# guac_v1.net
KiCad netlist of a schematic drawn in EAGLE
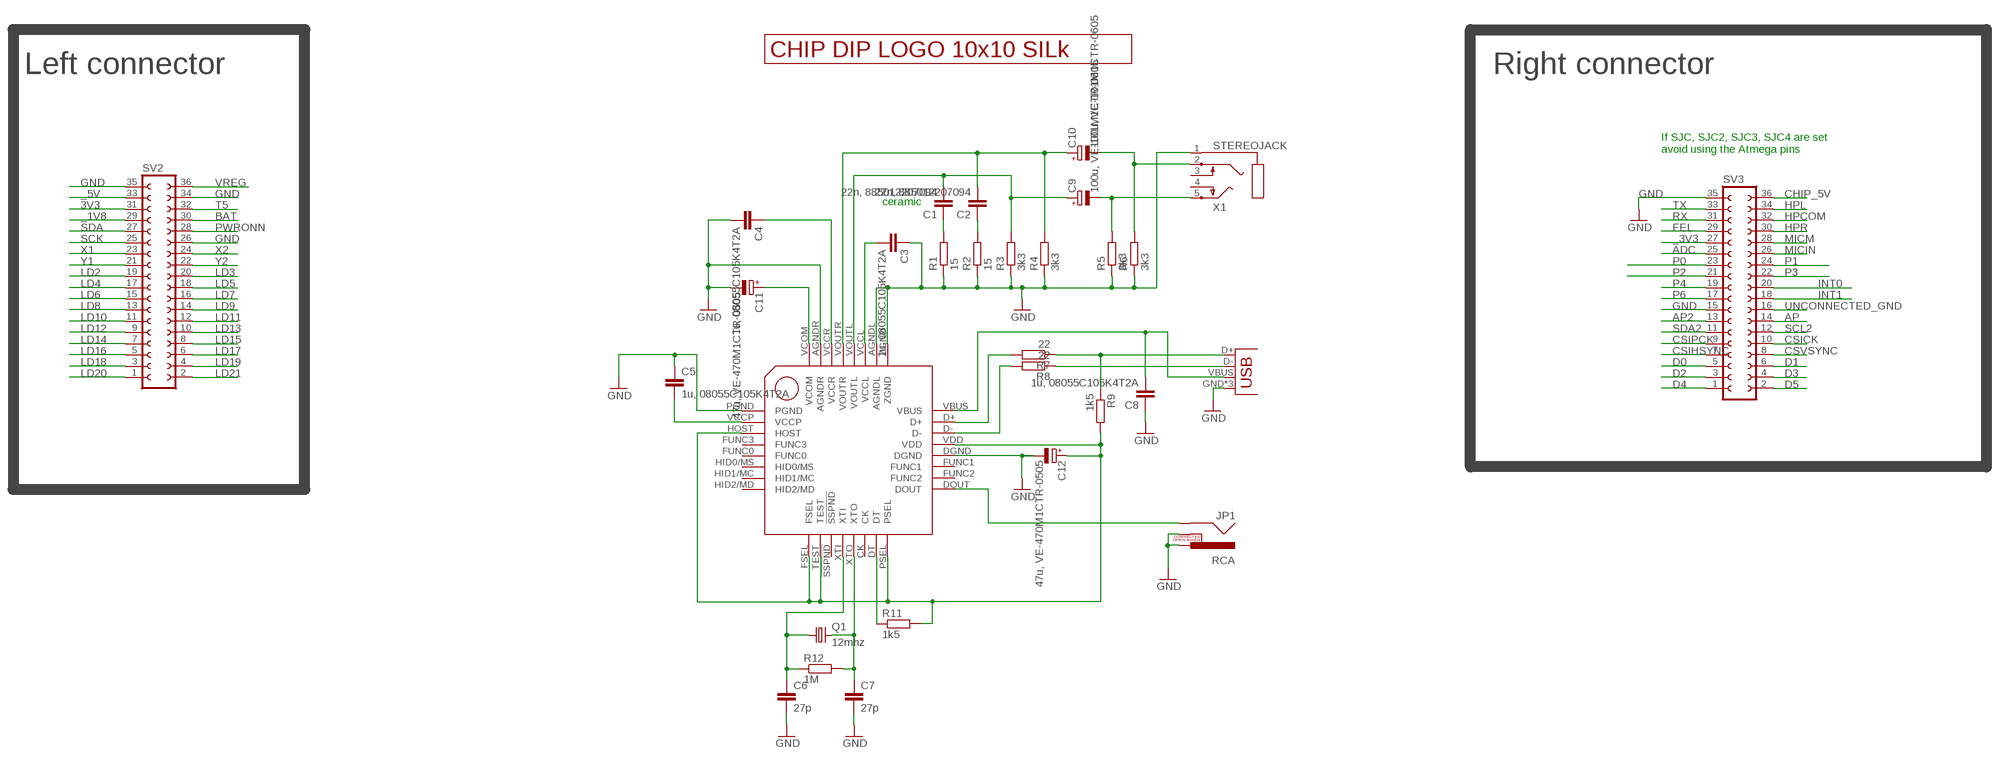
[diagram p0: schematic, sheet 1]

(export (version "E")
  (design (tool "Eeschema 10.0.6"))
  (components
    (comp (ref "C1")
      (value "22n, 885012207094")
      (footprint "eagle-import:C0805")
      (libsource (lib "eagle-import") (part "C-EUC0805"))
    )
    (comp (ref "C2")
      (value "22n, 885012207094")
      (footprint "eagle-import:C0805")
      (libsource (lib "eagle-import") (part "C-EUC0805"))
    )
    (comp (ref "C3")
      (value "1u, 08055C105K4T2A")
      (footprint "eagle-import:C0805")
      (libsource (lib "eagle-import") (part "C-EUC0805"))
    )
    (comp (ref "C4")
      (value "1u, 08055C105K4T2A")
      (footprint "eagle-import:C0805")
      (libsource (lib "eagle-import") (part "C-EUC0805"))
    )
    (comp (ref "C5")
      (value "1u, 08055C105K4T2A")
      (footprint "eagle-import:C0805")
      (libsource (lib "eagle-import") (part "C-EUC0805"))
    )
    (comp (ref "C6")
      (value "27p")
      (footprint "eagle-import:C0805")
      (libsource (lib "eagle-import") (part "C-EUC0805"))
    )
    (comp (ref "C7")
      (value "27p")
      (footprint "eagle-import:C0805")
      (libsource (lib "eagle-import") (part "C-EUC0805"))
    )
    (comp (ref "C8")
      (value "1u, 08055C105K4T2A")
      (footprint "eagle-import:C0805")
      (libsource (lib "eagle-import") (part "C-EUC0805"))
    )
    (comp (ref "C9")
      (value "100u, VE-101M1CTR-0605")
      (footprint "eagle-import:140CLH-0810")
      (libsource (lib "eagle-import") (part "CPOL-EU140CLH-0810"))
    )
    (comp (ref "C10")
      (value "100u, VE-101M1CTR-0605")
      (footprint "eagle-import:140CLH-0810")
      (libsource (lib "eagle-import") (part "CPOL-EU140CLH-0810"))
    )
    (comp (ref "C11")
      (value "47u, VE-470M1CTR-0505")
      (footprint "eagle-import:140CLH-0810")
      (libsource (lib "eagle-import") (part "CPOL-EU140CLH-0810"))
    )
    (comp (ref "C12")
      (value "47u, VE-470M1CTR-0505")
      (footprint "eagle-import:140CLH-0810")
      (libsource (lib "eagle-import") (part "CPOL-EU140CLH-0810"))
    )
    (comp (ref "JP1")
      (value "RCA")
      (footprint "eagle-import:RCA")
      (libsource (lib "eagle-import") (part "RCA"))
    )
    (comp (ref "Q1")
      (value "12mhz")
      (footprint "eagle-import:HC49UP")
      (libsource (lib "eagle-import") (part "CRYSTALHC49UP"))
    )
    (comp (ref "R1")
      (value "15")
      (footprint "eagle-import:M0805")
      (libsource (lib "eagle-import") (part "R-EU_M0805"))
    )
    (comp (ref "R2")
      (value "15")
      (footprint "eagle-import:M0805")
      (libsource (lib "eagle-import") (part "R-EU_M0805"))
    )
    (comp (ref "R3")
      (value "3k3")
      (footprint "eagle-import:M0805")
      (libsource (lib "eagle-import") (part "R-EU_M0805"))
    )
    (comp (ref "R4")
      (value "3k3")
      (footprint "eagle-import:M0805")
      (libsource (lib "eagle-import") (part "R-EU_M0805"))
    )
    (comp (ref "R5")
      (value "3k3")
      (footprint "eagle-import:M0805")
      (libsource (lib "eagle-import") (part "R-EU_M0805"))
    )
    (comp (ref "R6")
      (value "3k3")
      (footprint "eagle-import:M0805")
      (libsource (lib "eagle-import") (part "R-EU_M0805"))
    )
    (comp (ref "R7")
      (value "22")
      (footprint "eagle-import:M0805")
      (libsource (lib "eagle-import") (part "R-EU_M0805"))
    )
    (comp (ref "R8")
      (value "22")
      (footprint "eagle-import:M0805")
      (libsource (lib "eagle-import") (part "R-EU_M0805"))
    )
    (comp (ref "R9")
      (value "1k5")
      (footprint "eagle-import:M0805")
      (libsource (lib "eagle-import") (part "R-EU_M0805"))
    )
    (comp (ref "R11")
      (value "1k5")
      (footprint "eagle-import:M0805")
      (libsource (lib "eagle-import") (part "R-EU_M0805"))
    )
    (comp (ref "R12")
      (value "1M")
      (footprint "eagle-import:M0805")
      (libsource (lib "eagle-import") (part "R-EU_M0805"))
    )
    (comp (ref "SV2")
      (value "FE18-2")
      (footprint "eagle-import:FE18-2")
      (libsource (lib "eagle-import") (part "FE18-2"))
    )
    (comp (ref "SV3")
      (value "FE18-2")
      (footprint "eagle-import:FE18-2")
      (libsource (lib "eagle-import") (part "FE18-2"))
    )
    (comp (ref "U$1")
      (value "PCM2706")
      (footprint "eagle-import:TQFP32-08")
      (libsource (lib "eagle-import") (part "PCM2706"))
    )
    (comp (ref "U$3")
      (value "LOGO_10X10_SILK")
      (footprint "eagle-import:LOGO_10X10_SILK")
      (libsource (lib "eagle-import") (part "LOGO_10X10_SILK"))
    )
    (comp (ref "USB")
      (value "USBUSB-MICROB-SMT-DIP")
      (footprint "eagle-import:USB-MICROB-SMT-DIP")
      (libsource (lib "eagle-import") (part "USBUSB-MICROB-SMT-DIP"))
    )
    (comp (ref "X1")
      (value "STEREOJACK")
      (footprint "eagle-import:STX3100")
      (libsource (lib "eagle-import") (part "STEREOJACK"))
    )
  )
  (nets
    (net (code "1") (name "/3V3") (class "Default")
      (node (ref "SV2") (pin "31") (pinfunction "31_31") (pintype "passive"))
    )
    (net (code "2") (name "/ADC") (class "Default")
      (node (ref "SV3") (pin "25") (pinfunction "25_25") (pintype "passive"))
    )
    (net (code "3") (name "/AP") (class "Default")
      (node (ref "SV3") (pin "14") (pinfunction "14_14") (pintype "passive"))
    )
    (net (code "4") (name "/AP2") (class "Default")
      (node (ref "SV3") (pin "13") (pinfunction "13_13") (pintype "passive"))
    )
    (net (code "5") (name "/BAT") (class "Default")
      (node (ref "SV2") (pin "30") (pinfunction "30_30") (pintype "passive"))
    )
    (net (code "6") (name "/CHIP_5V") (class "Default")
      (node (ref "SV3") (pin "36") (pinfunction "36_36") (pintype "passive"))
    )
    (net (code "7") (name "/CSICK") (class "Default")
      (node (ref "SV3") (pin "10") (pinfunction "10_10") (pintype "passive"))
    )
    (net (code "8") (name "/CSIHSYNC") (class "Default")
      (node (ref "SV3") (pin "7") (pinfunction "7_7") (pintype "passive"))
    )
    (net (code "9") (name "/CSIPCK") (class "Default")
      (node (ref "SV3") (pin "9") (pinfunction "9_9") (pintype "passive"))
    )
    (net (code "10") (name "/CSVSYNC") (class "Default")
      (node (ref "SV3") (pin "8") (pinfunction "8_8") (pintype "passive"))
    )
    (net (code "11") (name "/D0") (class "Default")
      (node (ref "SV3") (pin "5") (pinfunction "5_5") (pintype "passive"))
    )
    (net (code "12") (name "/D1") (class "Default")
      (node (ref "SV3") (pin "6") (pinfunction "6_6") (pintype "passive"))
    )
    (net (code "13") (name "/D2") (class "Default")
      (node (ref "SV3") (pin "3") (pinfunction "3_3") (pintype "passive"))
    )
    (net (code "14") (name "/D3") (class "Default")
      (node (ref "SV3") (pin "4") (pinfunction "4_4") (pintype "passive"))
    )
    (net (code "15") (name "/D4") (class "Default")
      (node (ref "SV3") (pin "1") (pinfunction "1_1") (pintype "passive"))
    )
    (net (code "16") (name "/D5") (class "Default")
      (node (ref "SV3") (pin "2") (pinfunction "2_2") (pintype "passive"))
    )
    (net (code "17") (name "/FEL") (class "Default")
      (node (ref "SV3") (pin "29") (pinfunction "29_29") (pintype "passive"))
    )
    (net (code "18") (name "/HPCOM") (class "Default")
      (node (ref "SV3") (pin "32") (pinfunction "32_32") (pintype "passive"))
    )
    (net (code "19") (name "/HPL") (class "Default")
      (node (ref "SV3") (pin "34") (pinfunction "34_34") (pintype "passive"))
    )
    (net (code "20") (name "/HPR") (class "Default")
      (node (ref "SV3") (pin "30") (pinfunction "30_30") (pintype "passive"))
    )
    (net (code "21") (name "/INT0") (class "Default")
      (node (ref "SV3") (pin "20") (pinfunction "20_20") (pintype "passive"))
    )
    (net (code "22") (name "/INT1") (class "Default")
      (node (ref "SV3") (pin "18") (pinfunction "18_18") (pintype "passive"))
    )
    (net (code "23") (name "/LD2") (class "Default")
      (node (ref "SV2") (pin "19") (pinfunction "19_19") (pintype "passive"))
    )
    (net (code "24") (name "/LD3") (class "Default")
      (node (ref "SV2") (pin "20") (pinfunction "20_20") (pintype "passive"))
    )
    (net (code "25") (name "/LD4") (class "Default")
      (node (ref "SV2") (pin "17") (pinfunction "17_17") (pintype "passive"))
    )
    (net (code "26") (name "/LD5") (class "Default")
      (node (ref "SV2") (pin "18") (pinfunction "18_18") (pintype "passive"))
    )
    (net (code "27") (name "/LD6") (class "Default")
      (node (ref "SV2") (pin "15") (pinfunction "15_15") (pintype "passive"))
    )
    (net (code "28") (name "/LD7") (class "Default")
      (node (ref "SV2") (pin "16") (pinfunction "16_16") (pintype "passive"))
    )
    (net (code "29") (name "/LD8") (class "Default")
      (node (ref "SV2") (pin "13") (pinfunction "13_13") (pintype "passive"))
    )
    (net (code "30") (name "/LD9") (class "Default")
      (node (ref "SV2") (pin "14") (pinfunction "14_14") (pintype "passive"))
    )
    (net (code "31") (name "/LD10") (class "Default")
      (node (ref "SV2") (pin "11") (pinfunction "11_11") (pintype "passive"))
    )
    (net (code "32") (name "/LD11") (class "Default")
      (node (ref "SV2") (pin "12") (pinfunction "12_12") (pintype "passive"))
    )
    (net (code "33") (name "/LD12") (class "Default")
      (node (ref "SV2") (pin "9") (pinfunction "9_9") (pintype "passive"))
    )
    (net (code "34") (name "/LD13") (class "Default")
      (node (ref "SV2") (pin "10") (pinfunction "10_10") (pintype "passive"))
    )
    (net (code "35") (name "/LD14") (class "Default")
      (node (ref "SV2") (pin "7") (pinfunction "7_7") (pintype "passive"))
    )
    (net (code "36") (name "/LD15") (class "Default")
      (node (ref "SV2") (pin "8") (pinfunction "8_8") (pintype "passive"))
    )
    (net (code "37") (name "/LD16") (class "Default")
      (node (ref "SV2") (pin "5") (pinfunction "5_5") (pintype "passive"))
    )
    (net (code "38") (name "/LD17") (class "Default")
      (node (ref "SV2") (pin "6") (pinfunction "6_6") (pintype "passive"))
    )
    (net (code "39") (name "/LD18") (class "Default")
      (node (ref "SV2") (pin "3") (pinfunction "3_3") (pintype "passive"))
    )
    (net (code "40") (name "/LD19") (class "Default")
      (node (ref "SV2") (pin "4") (pinfunction "4_4") (pintype "passive"))
    )
    (net (code "41") (name "/LD20") (class "Default")
      (node (ref "SV2") (pin "1") (pinfunction "1_1") (pintype "passive"))
    )
    (net (code "42") (name "/LD21") (class "Default")
      (node (ref "SV2") (pin "2") (pinfunction "2_2") (pintype "passive"))
    )
    (net (code "43") (name "/MICIN") (class "Default")
      (node (ref "SV3") (pin "26") (pinfunction "26_26") (pintype "passive"))
    )
    (net (code "44") (name "/MICM") (class "Default")
      (node (ref "SV3") (pin "28") (pinfunction "28_28") (pintype "passive"))
    )
    (net (code "45") (name "/P0") (class "Default")
      (node (ref "SV3") (pin "23") (pinfunction "23_23") (pintype "passive"))
    )
    (net (code "46") (name "/P1") (class "Default")
      (node (ref "SV3") (pin "24") (pinfunction "24_24") (pintype "passive"))
    )
    (net (code "47") (name "/P2") (class "Default")
      (node (ref "SV3") (pin "21") (pinfunction "21_21") (pintype "passive"))
    )
    (net (code "48") (name "/P3") (class "Default")
      (node (ref "SV3") (pin "22") (pinfunction "22_22") (pintype "passive"))
    )
    (net (code "49") (name "/P4") (class "Default")
      (node (ref "SV3") (pin "19") (pinfunction "19_19") (pintype "passive"))
    )
    (net (code "50") (name "/P6") (class "Default")
      (node (ref "SV3") (pin "17") (pinfunction "17_17") (pintype "passive"))
    )
    (net (code "51") (name "/PWRONN") (class "Default")
      (node (ref "SV2") (pin "28") (pinfunction "28_28") (pintype "passive"))
    )
    (net (code "52") (name "/RX") (class "Default")
      (node (ref "SV3") (pin "31") (pinfunction "31_31") (pintype "passive"))
    )
    (net (code "53") (name "/SCK") (class "Default")
      (node (ref "SV2") (pin "25") (pinfunction "25_25") (pintype "passive"))
    )
    (net (code "54") (name "/SCL2") (class "Default")
      (node (ref "SV3") (pin "12") (pinfunction "12_12") (pintype "passive"))
    )
    (net (code "55") (name "/SDA") (class "Default")
      (node (ref "SV2") (pin "27") (pinfunction "27_27") (pintype "passive"))
    )
    (net (code "56") (name "/SDA2") (class "Default")
      (node (ref "SV3") (pin "11") (pinfunction "11_11") (pintype "passive"))
    )
    (net (code "57") (name "/T5") (class "Default")
      (node (ref "SV2") (pin "32") (pinfunction "32_32") (pintype "passive"))
    )
    (net (code "58") (name "/TX") (class "Default")
      (node (ref "SV3") (pin "33") (pinfunction "33_33") (pintype "passive"))
    )
    (net (code "59") (name "/UNCONNECTED_GND") (class "Default")
      (node (ref "SV3") (pin "16") (pinfunction "16_16") (pintype "passive"))
    )
    (net (code "60") (name "/VREG") (class "Default")
      (node (ref "SV2") (pin "36") (pinfunction "36_36") (pintype "passive"))
    )
    (net (code "61") (name "/X1") (class "Default")
      (node (ref "SV2") (pin "23") (pinfunction "23_23") (pintype "passive"))
    )
    (net (code "62") (name "/X2") (class "Default")
      (node (ref "SV2") (pin "24") (pinfunction "24_24") (pintype "passive"))
    )
    (net (code "63") (name "/Y1") (class "Default")
      (node (ref "SV2") (pin "21") (pinfunction "21_21") (pintype "passive"))
    )
    (net (code "64") (name "/Y2") (class "Default")
      (node (ref "SV2") (pin "22") (pinfunction "22_22") (pintype "passive"))
    )
    (net (code "65") (name "/_1V8") (class "Default")
      (node (ref "SV2") (pin "29") (pinfunction "29_29") (pintype "passive"))
    )
    (net (code "66") (name "/_3V3") (class "Default")
      (node (ref "SV3") (pin "27") (pinfunction "27_27") (pintype "passive"))
    )
    (net (code "67") (name "/_5V") (class "Default")
      (node (ref "SV2") (pin "33") (pinfunction "33_33") (pintype "passive"))
    )
    (net (code "68") (name "GND") (class "Default")
      (node (ref "C11") (pin "-") (pinfunction "-_-") (pintype "passive"))
      (node (ref "C12") (pin "-") (pinfunction "-_-") (pintype "passive"))
      (node (ref "C3") (pin "1") (pinfunction "1_1") (pintype "passive"))
      (node (ref "C4") (pin "2") (pinfunction "2_2") (pintype "passive"))
      (node (ref "C5") (pin "1") (pinfunction "1_1") (pintype "passive"))
      (node (ref "C6") (pin "2") (pinfunction "2_2") (pintype "passive"))
      (node (ref "C7") (pin "2") (pinfunction "2_2") (pintype "passive"))
      (node (ref "C8") (pin "1") (pinfunction "1_1") (pintype "passive"))
      (node (ref "JP1") (pin "PIN") (pinfunction "PIN_PIN") (pintype "bidirectional"))
      (node (ref "JP1") (pin "SWITCH") (pinfunction "SWITCH_SWITCH") (pintype "bidirectional"))
      (node (ref "R1") (pin "1") (pinfunction "1_1") (pintype "passive"))
      (node (ref "R2") (pin "1") (pinfunction "1_1") (pintype "passive"))
      (node (ref "R3") (pin "1") (pinfunction "1_1") (pintype "passive"))
      (node (ref "R4") (pin "1") (pinfunction "1_1") (pintype "passive"))
      (node (ref "R5") (pin "1") (pinfunction "1_1") (pintype "passive"))
      (node (ref "R6") (pin "1") (pinfunction "1_1") (pintype "passive"))
      (node (ref "SV2") (pin "26") (pinfunction "26_26") (pintype "passive"))
      (node (ref "SV2") (pin "34") (pinfunction "34_34") (pintype "passive"))
      (node (ref "SV2") (pin "35") (pinfunction "35_35") (pintype "passive"))
      (node (ref "SV3") (pin "15") (pinfunction "15_15") (pintype "passive"))
      (node (ref "SV3") (pin "35") (pinfunction "35_35") (pintype "passive"))
      (node (ref "U$1") (pin "AGNDL") (pinfunction "AGNDL_AGNDL") (pintype "power_in"))
      (node (ref "U$1") (pin "AGNDR") (pinfunction "AGNDR_AGNDR") (pintype "power_in"))
      (node (ref "U$1") (pin "DGND") (pinfunction "DGND_DGND") (pintype "power_in"))
      (node (ref "U$1") (pin "PGND") (pinfunction "PGND_PGND") (pintype "power_in"))
      (node (ref "U$1") (pin "ZGND") (pinfunction "ZGND_ZGND") (pintype "power_in"))
      (node (ref "USB") (pin "GND") (pinfunction "GND_GND") (pintype "bidirectional"))
      (node (ref "USB") (pin "MT1") (pinfunction "GND_MT1") (pintype "bidirectional"))
      (node (ref "USB") (pin "MT2") (pinfunction "GND_MT2") (pintype "bidirectional"))
      (node (ref "X1") (pin "1") (pinfunction "1_1") (pintype "passive"))
    )
    (net (code "69") (name "Net-(C1-Pad1)") (class "Default")
      (node (ref "C1") (pin "1") (pinfunction "1_1") (pintype "passive"))
      (node (ref "R1") (pin "2") (pinfunction "2_2") (pintype "passive"))
    )
    (net (code "70") (name "Net-(C1-Pad2)") (class "Default")
      (node (ref "C1") (pin "2") (pinfunction "2_2") (pintype "passive"))
      (node (ref "C9") (pin "+") (pinfunction "+_+") (pintype "passive"))
      (node (ref "R3") (pin "2") (pinfunction "2_2") (pintype "passive"))
      (node (ref "U$1") (pin "VOUTL") (pinfunction "VOUTL_VOUTL") (pintype "output"))
    )
    (net (code "71") (name "Net-(C2-Pad1)") (class "Default")
      (node (ref "C2") (pin "1") (pinfunction "1_1") (pintype "passive"))
      (node (ref "R2") (pin "2") (pinfunction "2_2") (pintype "passive"))
    )
    (net (code "72") (name "Net-(C3-Pad2)") (class "Default")
      (node (ref "C3") (pin "2") (pinfunction "2_2") (pintype "passive"))
      (node (ref "U$1") (pin "VCCL") (pinfunction "VCCL_VCCL") (pintype "power_in"))
    )
    (net (code "73") (name "Net-(C4-Pad1)") (class "Default")
      (node (ref "C4") (pin "1") (pinfunction "1_1") (pintype "passive"))
      (node (ref "U$1") (pin "VCCR") (pinfunction "VCCR_VCCR") (pintype "power_in"))
    )
    (net (code "74") (name "Net-(C5-Pad2)") (class "Default")
      (node (ref "C5") (pin "2") (pinfunction "2_2") (pintype "passive"))
      (node (ref "U$1") (pin "VCCP") (pinfunction "VCCP_VCCP") (pintype "power_in"))
    )
    (net (code "75") (name "Net-(C6-Pad1)") (class "Default")
      (node (ref "C6") (pin "1") (pinfunction "1_1") (pintype "passive"))
      (node (ref "Q1") (pin "1") (pinfunction "1_1") (pintype "passive"))
      (node (ref "R12") (pin "1") (pinfunction "1_1") (pintype "passive"))
      (node (ref "U$1") (pin "XTI") (pinfunction "XTI_XTI") (pintype "bidirectional"))
    )
    (net (code "76") (name "Net-(C7-Pad1)") (class "Default")
      (node (ref "C7") (pin "1") (pinfunction "1_1") (pintype "passive"))
      (node (ref "Q1") (pin "2") (pinfunction "2_2") (pintype "passive"))
      (node (ref "R12") (pin "2") (pinfunction "2_2") (pintype "passive"))
      (node (ref "U$1") (pin "XTO") (pinfunction "XTO_XTO") (pintype "bidirectional"))
    )
    (net (code "77") (name "Net-(C8-Pad2)") (class "Default")
      (node (ref "C8") (pin "2") (pinfunction "2_2") (pintype "passive"))
      (node (ref "U$1") (pin "VBUS") (pinfunction "VBUS_VBUS") (pintype "power_in"))
      (node (ref "USB") (pin "VBUS") (pinfunction "VBUS_VBUS") (pintype "bidirectional"))
    )
    (net (code "78") (name "Net-(C9-Pad-)") (class "Default")
      (node (ref "C9") (pin "-") (pinfunction "-_-") (pintype "passive"))
      (node (ref "R5") (pin "2") (pinfunction "2_2") (pintype "passive"))
      (node (ref "X1") (pin "5") (pinfunction "5_5") (pintype "passive"))
    )
    (net (code "79") (name "Net-(C10-Pad+)") (class "Default")
      (node (ref "C10") (pin "+") (pinfunction "+_+") (pintype "passive"))
      (node (ref "C2") (pin "2") (pinfunction "2_2") (pintype "passive"))
      (node (ref "R4") (pin "2") (pinfunction "2_2") (pintype "passive"))
      (node (ref "U$1") (pin "VOUTR") (pinfunction "VOUTR_VOUTR") (pintype "output"))
    )
    (net (code "80") (name "Net-(C10-Pad-)") (class "Default")
      (node (ref "C10") (pin "-") (pinfunction "-_-") (pintype "passive"))
      (node (ref "R6") (pin "2") (pinfunction "2_2") (pintype "passive"))
      (node (ref "X1") (pin "2") (pinfunction "2_2") (pintype "passive"))
    )
    (net (code "81") (name "Net-(C11-Pad+)") (class "Default")
      (node (ref "C11") (pin "+") (pinfunction "+_+") (pintype "passive"))
      (node (ref "U$1") (pin "VCOM") (pinfunction "VCOM_VCOM") (pintype "power_in"))
    )
    (net (code "82") (name "Net-(C12-Pad+)") (class "Default")
      (node (ref "C12") (pin "+") (pinfunction "+_+") (pintype "passive"))
      (node (ref "R11") (pin "2") (pinfunction "2_2") (pintype "passive"))
      (node (ref "R9") (pin "2") (pinfunction "2_2") (pintype "passive"))
      (node (ref "U$1") (pin "FSEL") (pinfunction "FSEL_FSEL") (pintype "bidirectional"))
      (node (ref "U$1") (pin "HOST") (pinfunction "HOST_HOST") (pintype "power_in"))
      (node (ref "U$1") (pin "PSEL") (pinfunction "PSEL_PSEL") (pintype "bidirectional"))
      (node (ref "U$1") (pin "TEST") (pinfunction "TEST_TEST") (pintype "bidirectional"))
      (node (ref "U$1") (pin "VDD") (pinfunction "VDD_VDD") (pintype "power_in"))
    )
    (net (code "83") (name "Net-(JP1-PadSHELL)") (class "Default")
      (node (ref "JP1") (pin "SHELL") (pinfunction "SHELL_SHELL") (pintype "bidirectional"))
      (node (ref "U$1") (pin "DOUT") (pinfunction "DOUT_DOUT") (pintype "bidirectional"))
    )
    (net (code "84") (name "Net-(R7-Pad1)") (class "Default")
      (node (ref "R7") (pin "1") (pinfunction "1_1") (pintype "passive"))
      (node (ref "R9") (pin "1") (pinfunction "1_1") (pintype "passive"))
      (node (ref "USB") (pin "D+") (pinfunction "D+_D+") (pintype "bidirectional"))
    )
    (net (code "85") (name "Net-(R7-Pad2)") (class "Default")
      (node (ref "R7") (pin "2") (pinfunction "2_2") (pintype "passive"))
      (node (ref "U$1") (pin "D+") (pinfunction "D+_D+") (pintype "bidirectional"))
    )
    (net (code "86") (name "Net-(R8-Pad1)") (class "Default")
      (node (ref "R8") (pin "1") (pinfunction "1_1") (pintype "passive"))
      (node (ref "USB") (pin "D-") (pinfunction "D-_D-") (pintype "bidirectional"))
    )
    (net (code "87") (name "Net-(R8-Pad2)") (class "Default")
      (node (ref "R8") (pin "2") (pinfunction "2_2") (pintype "passive"))
      (node (ref "U$1") (pin "D-") (pinfunction "D-_D-") (pintype "bidirectional"))
    )
    (net (code "88") (name "Net-(R11-Pad1)") (class "Default")
      (node (ref "R11") (pin "1") (pinfunction "1_1") (pintype "passive"))
      (node (ref "U$1") (pin "DT") (pinfunction "DT_DT") (pintype "bidirectional"))
    )
    (net (code "89") (name "unconnected-(U$1-PadCK)") (class "Default")
      (node (ref "U$1") (pin "CK") (pinfunction "CK_CK") (pintype "bidirectional"))
    )
    (net (code "90") (name "unconnected-(U$1-PadFUNC0)") (class "Default")
      (node (ref "U$1") (pin "FUNC0") (pinfunction "FUNC0_FUNC0") (pintype "bidirectional"))
    )
    (net (code "91") (name "unconnected-(U$1-PadFUNC1)") (class "Default")
      (node (ref "U$1") (pin "FUNC1") (pinfunction "FUNC1_FUNC1") (pintype "bidirectional"))
    )
    (net (code "92") (name "unconnected-(U$1-PadFUNC2)") (class "Default")
      (node (ref "U$1") (pin "FUNC2") (pinfunction "FUNC2_FUNC2") (pintype "bidirectional"))
    )
    (net (code "93") (name "unconnected-(U$1-PadFUNC3)") (class "Default")
      (node (ref "U$1") (pin "FUNC3") (pinfunction "FUNC3_FUNC3") (pintype "bidirectional"))
    )
    (net (code "94") (name "unconnected-(U$1-PadHID0{slash}MS)") (class "Default")
      (node (ref "U$1") (pin "HID0/MS") (pinfunction "HID0/MS_HID0/MS") (pintype "bidirectional"))
    )
    (net (code "95") (name "unconnected-(U$1-PadHID1{slash}MC)") (class "Default")
      (node (ref "U$1") (pin "HID1/MC") (pinfunction "HID1/MC_HID1/MC") (pintype "bidirectional"))
    )
    (net (code "96") (name "unconnected-(U$1-PadHID2{slash}MD)") (class "Default")
      (node (ref "U$1") (pin "HID2/MD") (pinfunction "HID2/MD_HID2/MD") (pintype "bidirectional"))
    )
    (net (code "97") (name "unconnected-(U$1-~{SSPND}-Pad!SSPND)") (class "Default")
      (node (ref "U$1") (pin "!SSPND") (pinfunction "~{SSPND}_!SSPND") (pintype "bidirectional"))
    )
    (net (code "98") (name "unconnected-(X1-Pad3)") (class "Default")
      (node (ref "X1") (pin "3") (pinfunction "3_3") (pintype "passive"))
    )
    (net (code "99") (name "unconnected-(X1-Pad4)") (class "Default")
      (node (ref "X1") (pin "4") (pinfunction "4_4") (pintype "passive"))
    )
  )
)
